# MCU.net
KiCad netlist of a schematic drawn in Altium Designer
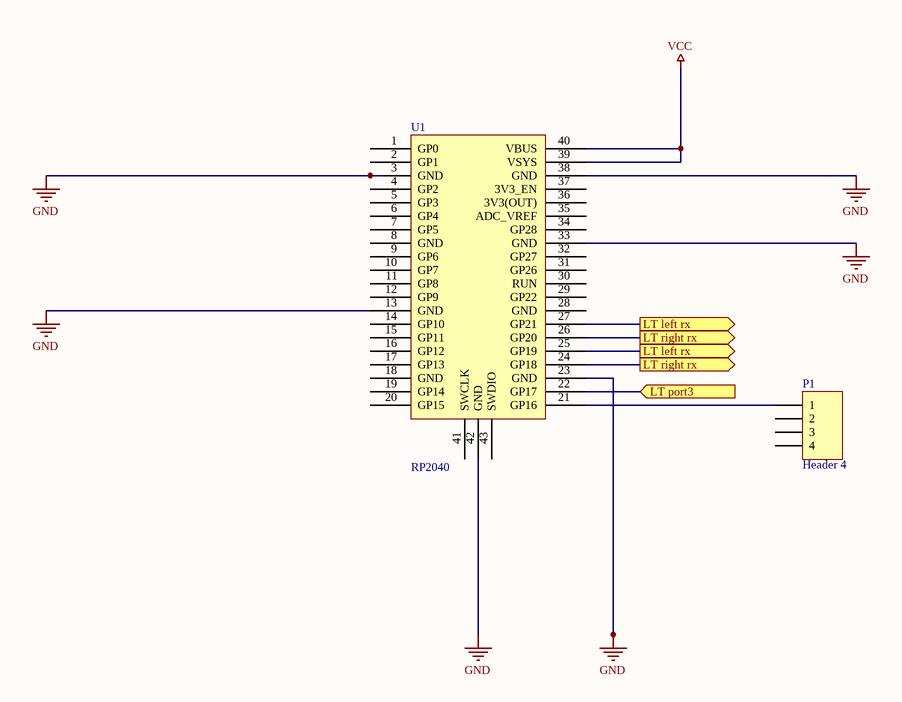
[diagram p0: MCU.SchDoc]

(export (version "E")
  (design (tool "Eeschema 10.0.6"))
  (components
    (comp (ref "P1")
      (value "Header 4")
      (footprint "HDR1X4")
      (description "Header, 4-Pin")
      (fields (field (name "PUBLISHER") "Altium Limited"))
      (libsource (lib "Miscellaneous+Connectors") (part "Header 4"))
    )
    (comp (ref "U1")
      (value "RP2040")
      (footprint "PCBComponent_1")
      (libsource (lib "PICO_sch") (part "Component_1"))
    )
  )
  (nets
    (net (code "1") (name "/LT left rx") (class "Default")
      (node (ref "U1") (pin "25") (pinfunction "GP19_25") (pintype "passive"))
      (node (ref "U1") (pin "27") (pinfunction "GP21_27") (pintype "passive"))
    )
    (net (code "2") (name "/LT port3") (class "Default")
      (node (ref "U1") (pin "22") (pinfunction "GP17_22") (pintype "passive"))
    )
    (net (code "3") (name "/LT right rx") (class "Default")
      (node (ref "U1") (pin "24") (pinfunction "GP18_24") (pintype "passive"))
      (node (ref "U1") (pin "26") (pinfunction "GP20_26") (pintype "passive"))
    )
    (net (code "4") (name "GND") (class "Default")
      (node (ref "U1") (pin "13") (pinfunction "GND_13") (pintype "passive"))
      (node (ref "U1") (pin "23") (pinfunction "GND_23") (pintype "passive"))
      (node (ref "U1") (pin "3") (pinfunction "GND_3") (pintype "passive"))
      (node (ref "U1") (pin "33") (pinfunction "GND_33") (pintype "passive"))
      (node (ref "U1") (pin "38") (pinfunction "GND_38") (pintype "passive"))
      (node (ref "U1") (pin "42") (pinfunction "GND_42") (pintype "passive"))
    )
    (net (code "5") (name "Net-(U1-GP16)") (class "Default")
      (node (ref "P1") (pin "1") (pinfunction "1_1") (pintype "passive"))
      (node (ref "U1") (pin "21") (pinfunction "GP16_21") (pintype "passive"))
    )
    (net (code "6") (name "VCC") (class "Default")
      (node (ref "U1") (pin "39") (pinfunction "VSYS_39") (pintype "passive"))
      (node (ref "U1") (pin "40") (pinfunction "VBUS_40") (pintype "passive"))
    )
    (net (code "7") (name "unconnected-(P1-Pad2)") (class "Default")
      (node (ref "P1") (pin "2") (pinfunction "2_2") (pintype "passive"))
    )
    (net (code "8") (name "unconnected-(P1-Pad3)") (class "Default")
      (node (ref "P1") (pin "3") (pinfunction "3_3") (pintype "passive"))
    )
    (net (code "9") (name "unconnected-(P1-Pad4)") (class "Default")
      (node (ref "P1") (pin "4") (pinfunction "4_4") (pintype "passive"))
    )
    (net (code "10") (name "unconnected-(U1-3V3(OUT)-Pad36)") (class "Default")
      (node (ref "U1") (pin "36") (pinfunction "3V3(OUT)_36") (pintype "passive"))
    )
    (net (code "11") (name "unconnected-(U1-3V3_EN-Pad37)") (class "Default")
      (node (ref "U1") (pin "37") (pinfunction "3V3_EN_37") (pintype "passive"))
    )
    (net (code "12") (name "unconnected-(U1-ADC_VREF-Pad35)") (class "Default")
      (node (ref "U1") (pin "35") (pinfunction "ADC_VREF_35") (pintype "passive"))
    )
    (net (code "13") (name "unconnected-(U1-GND-Pad8)") (class "Default")
      (node (ref "U1") (pin "8") (pinfunction "GND_8") (pintype "passive"))
    )
    (net (code "14") (name "unconnected-(U1-GND-Pad18)") (class "Default")
      (node (ref "U1") (pin "18") (pinfunction "GND_18") (pintype "passive"))
    )
    (net (code "15") (name "unconnected-(U1-GND-Pad28)") (class "Default")
      (node (ref "U1") (pin "28") (pinfunction "GND_28") (pintype "passive"))
    )
    (net (code "16") (name "unconnected-(U1-GP0-Pad1)") (class "Default")
      (node (ref "U1") (pin "1") (pinfunction "GP0_1") (pintype "passive"))
    )
    (net (code "17") (name "unconnected-(U1-GP1-Pad2)") (class "Default")
      (node (ref "U1") (pin "2") (pinfunction "GP1_2") (pintype "passive"))
    )
    (net (code "18") (name "unconnected-(U1-GP2-Pad4)") (class "Default")
      (node (ref "U1") (pin "4") (pinfunction "GP2_4") (pintype "passive"))
    )
    (net (code "19") (name "unconnected-(U1-GP3-Pad5)") (class "Default")
      (node (ref "U1") (pin "5") (pinfunction "GP3_5") (pintype "passive"))
    )
    (net (code "20") (name "unconnected-(U1-GP4-Pad6)") (class "Default")
      (node (ref "U1") (pin "6") (pinfunction "GP4_6") (pintype "passive"))
    )
    (net (code "21") (name "unconnected-(U1-GP5-Pad7)") (class "Default")
      (node (ref "U1") (pin "7") (pinfunction "GP5_7") (pintype "passive"))
    )
    (net (code "22") (name "unconnected-(U1-GP6-Pad9)") (class "Default")
      (node (ref "U1") (pin "9") (pinfunction "GP6_9") (pintype "passive"))
    )
    (net (code "23") (name "unconnected-(U1-GP7-Pad10)") (class "Default")
      (node (ref "U1") (pin "10") (pinfunction "GP7_10") (pintype "passive"))
    )
    (net (code "24") (name "unconnected-(U1-GP8-Pad11)") (class "Default")
      (node (ref "U1") (pin "11") (pinfunction "GP8_11") (pintype "passive"))
    )
    (net (code "25") (name "unconnected-(U1-GP9-Pad12)") (class "Default")
      (node (ref "U1") (pin "12") (pinfunction "GP9_12") (pintype "passive"))
    )
    (net (code "26") (name "unconnected-(U1-GP10-Pad14)") (class "Default")
      (node (ref "U1") (pin "14") (pinfunction "GP10_14") (pintype "passive"))
    )
    (net (code "27") (name "unconnected-(U1-GP11-Pad15)") (class "Default")
      (node (ref "U1") (pin "15") (pinfunction "GP11_15") (pintype "passive"))
    )
    (net (code "28") (name "unconnected-(U1-GP12-Pad16)") (class "Default")
      (node (ref "U1") (pin "16") (pinfunction "GP12_16") (pintype "passive"))
    )
    (net (code "29") (name "unconnected-(U1-GP13-Pad17)") (class "Default")
      (node (ref "U1") (pin "17") (pinfunction "GP13_17") (pintype "passive"))
    )
    (net (code "30") (name "unconnected-(U1-GP14-Pad19)") (class "Default")
      (node (ref "U1") (pin "19") (pinfunction "GP14_19") (pintype "passive"))
    )
    (net (code "31") (name "unconnected-(U1-GP15-Pad20)") (class "Default")
      (node (ref "U1") (pin "20") (pinfunction "GP15_20") (pintype "passive"))
    )
    (net (code "32") (name "unconnected-(U1-GP22-Pad29)") (class "Default")
      (node (ref "U1") (pin "29") (pinfunction "GP22_29") (pintype "passive"))
    )
    (net (code "33") (name "unconnected-(U1-GP26-Pad31)") (class "Default")
      (node (ref "U1") (pin "31") (pinfunction "GP26_31") (pintype "passive"))
    )
    (net (code "34") (name "unconnected-(U1-GP27-Pad32)") (class "Default")
      (node (ref "U1") (pin "32") (pinfunction "GP27_32") (pintype "passive"))
    )
    (net (code "35") (name "unconnected-(U1-GP28-Pad34)") (class "Default")
      (node (ref "U1") (pin "34") (pinfunction "GP28_34") (pintype "passive"))
    )
    (net (code "36") (name "unconnected-(U1-RUN-Pad30)") (class "Default")
      (node (ref "U1") (pin "30") (pinfunction "RUN_30") (pintype "passive"))
    )
    (net (code "37") (name "unconnected-(U1-SWCLK-Pad41)") (class "Default")
      (node (ref "U1") (pin "41") (pinfunction "SWCLK_41") (pintype "passive"))
    )
    (net (code "38") (name "unconnected-(U1-SWDIO-Pad43)") (class "Default")
      (node (ref "U1") (pin "43") (pinfunction "SWDIO_43") (pintype "passive"))
    )
  )
)
